# mosfet_buck_inverterV2.net
KiCad netlist of a schematic drawn in EAGLE
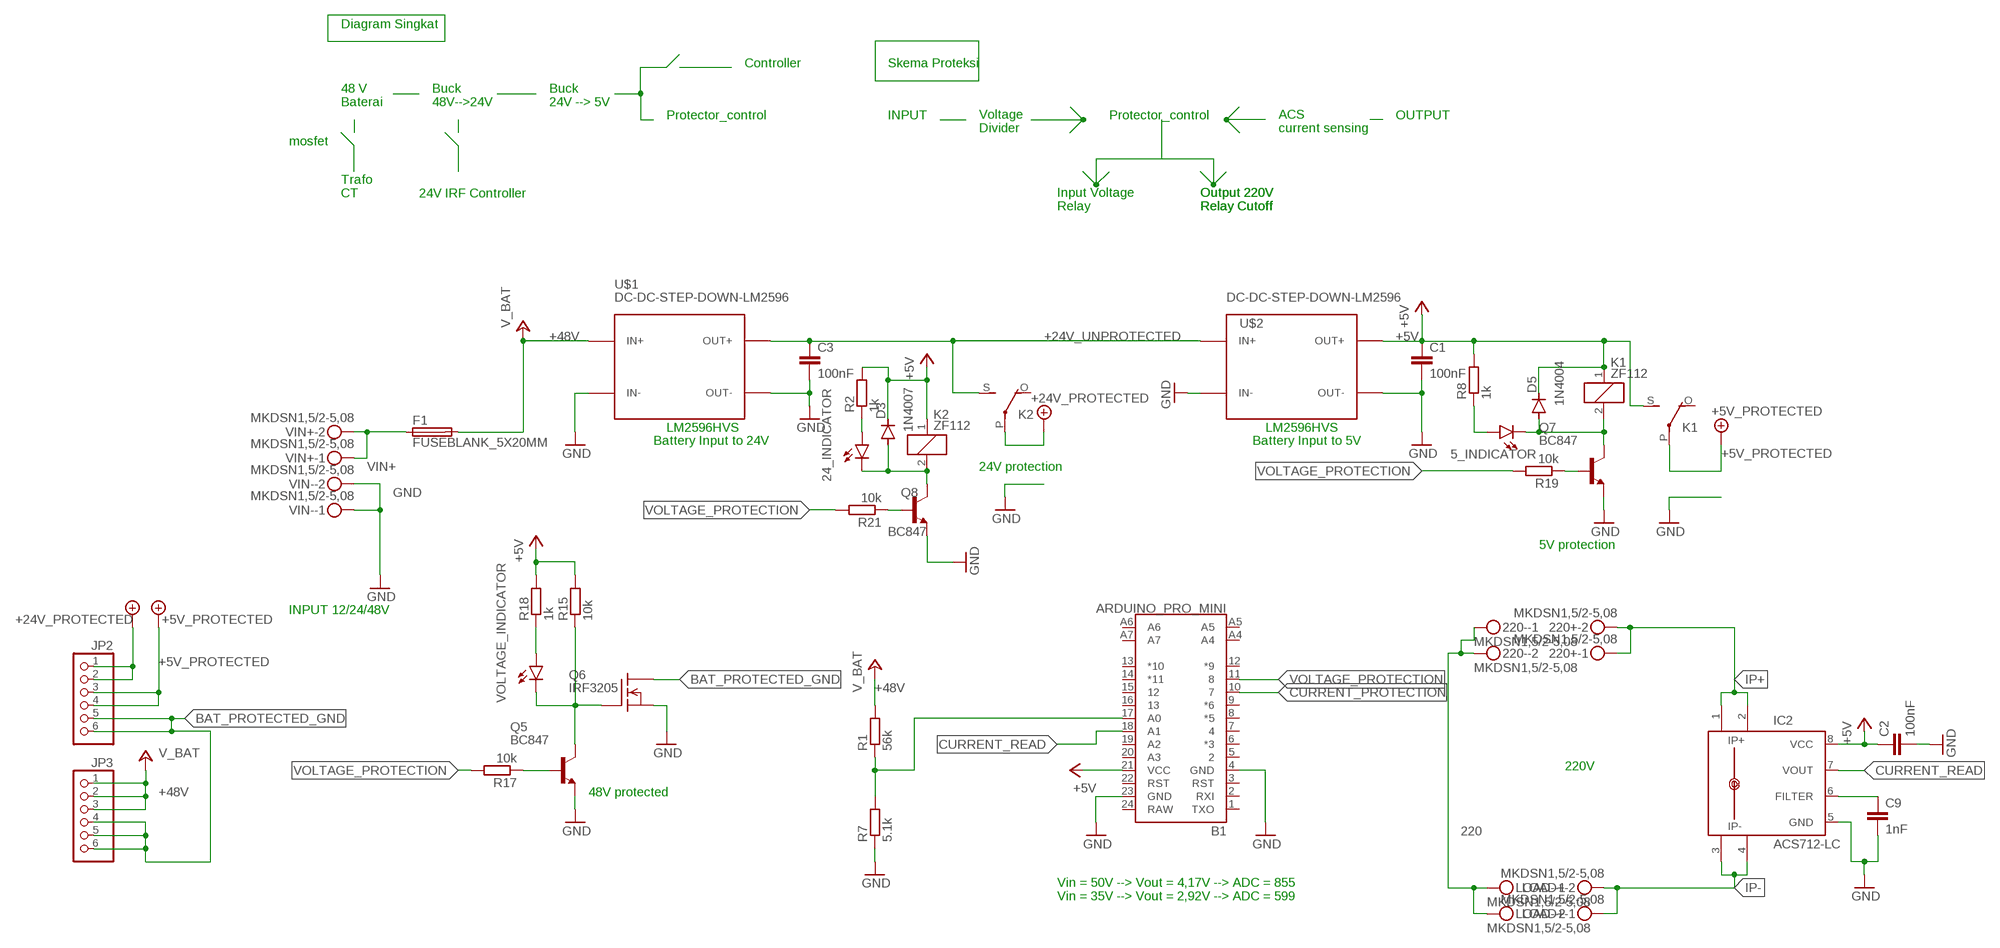
[diagram p0: schematic, sheet 1]

(export (version "E")
  (design (tool "Eeschema 10.0.6"))
  (components
    (comp (ref "5_INDICATOR")
      (value "LED1206")
      (footprint "eagle-import:LED-1206")
      (libsource (lib "eagle-import") (part "LED1206"))
    )
    (comp (ref "24_INDICATOR")
      (value "LED1206")
      (footprint "eagle-import:LED-1206")
      (libsource (lib "eagle-import") (part "LED1206"))
    )
    (comp (ref "220+")
      (value "MKDSN1,5/2-5,08")
      (footprint "eagle-import:MKDSN1,5_2-5,08")
      (libsource (lib "eagle-import") (part "MKDSN1,5/2-5,08"))
    )
    (comp (ref "220-")
      (value "MKDSN1,5/2-5,08")
      (footprint "eagle-import:MKDSN1,5_2-5,08")
      (libsource (lib "eagle-import") (part "MKDSN1,5/2-5,08"))
    )
    (comp (ref "B1")
      (value "ARDUINO_PRO_MINI")
      (footprint "eagle-import:ARDUINO_PRO_MINI")
      (libsource (lib "eagle-import") (part "ARDUINO_PRO_MINI"))
    )
    (comp (ref "C1")
      (value "100nF")
      (footprint "eagle-import:C0805K")
      (libsource (lib "eagle-import") (part "C-EUC0805K"))
    )
    (comp (ref "C2")
      (value "100nF")
      (footprint "eagle-import:C0805K")
      (libsource (lib "eagle-import") (part "C-EUC0805K"))
    )
    (comp (ref "C3")
      (value "100nF")
      (footprint "eagle-import:C0805K")
      (libsource (lib "eagle-import") (part "C-EUC0805K"))
    )
    (comp (ref "C9")
      (value "1nF")
      (footprint "eagle-import:C0805K")
      (libsource (lib "eagle-import") (part "C-EUC0805K"))
    )
    (comp (ref "D3")
      (value "1N4007")
      (footprint "eagle-import:DO41-10")
      (libsource (lib "eagle-import") (part "1N4004"))
    )
    (comp (ref "D5")
      (value "1N4004")
      (footprint "eagle-import:DO41-10")
      (libsource (lib "eagle-import") (part "1N4004"))
    )
    (comp (ref "F1")
      (value "FUSEBLANK_5X20MM")
      (footprint "eagle-import:FUSE_HOLDER_5X20MM")
      (libsource (lib "eagle-import") (part "FUSEBLANK_5X20MM"))
    )
    (comp (ref "IC2")
      (value "ACS712-LC")
      (footprint "eagle-import:SOIC8")
      (fields (field (name "SPICEPREFIX") "X"))
      (libsource (lib "eagle-import") (part "ACS712-LC"))
    )
    (comp (ref "JP2")
      (value "PINHD-1X6CLEAN")
      (footprint "eagle-import:1X06-CLEAN")
      (libsource (lib "eagle-import") (part "PINHD-1X6CLEAN"))
    )
    (comp (ref "JP3")
      (value "PINHD-1X6CLEAN")
      (footprint "eagle-import:1X06-CLEAN")
      (libsource (lib "eagle-import") (part "PINHD-1X6CLEAN"))
    )
    (comp (ref "K1")
      (value "ZF112")
      (footprint "eagle-import:ZF112")
      (libsource (lib "eagle-import") (part "ZF112"))
    )
    (comp (ref "K2")
      (value "ZF112")
      (footprint "eagle-import:ZF112")
      (libsource (lib "eagle-import") (part "ZF112"))
    )
    (comp (ref "LOAD+")
      (value "MKDSN1,5/2-5,08")
      (footprint "eagle-import:MKDSN1,5_2-5,08")
      (libsource (lib "eagle-import") (part "MKDSN1,5/2-5,08"))
    )
    (comp (ref "LOAD-")
      (value "MKDSN1,5/2-5,08")
      (footprint "eagle-import:MKDSN1,5_2-5,08")
      (libsource (lib "eagle-import") (part "MKDSN1,5/2-5,08"))
    )
    (comp (ref "Q5")
      (value "BC847")
      (footprint "eagle-import:SOT23")
      (libsource (lib "eagle-import") (part "BC847SMDA"))
    )
    (comp (ref "Q6")
      (value "IRF3205")
      (footprint "eagle-import:TO220")
      (libsource (lib "eagle-import") (part "IRF540"))
    )
    (comp (ref "Q7")
      (value "BC847")
      (footprint "eagle-import:SOT23")
      (libsource (lib "eagle-import") (part "BC847SMDA"))
    )
    (comp (ref "Q8")
      (value "BC847")
      (footprint "eagle-import:SOT23")
      (libsource (lib "eagle-import") (part "BC847SMDA"))
    )
    (comp (ref "R1")
      (value "56k")
      (footprint "eagle-import:R0805")
      (libsource (lib "eagle-import") (part "R-EU_R0805"))
    )
    (comp (ref "R2")
      (value "1k")
      (footprint "eagle-import:R0805")
      (libsource (lib "eagle-import") (part "R-EU_R0805"))
    )
    (comp (ref "R7")
      (value "5.1k")
      (footprint "eagle-import:R0805")
      (libsource (lib "eagle-import") (part "R-EU_R0805"))
    )
    (comp (ref "R8")
      (value "1k")
      (footprint "eagle-import:R0805")
      (libsource (lib "eagle-import") (part "R-EU_R0805"))
    )
    (comp (ref "R15")
      (value "10k")
      (footprint "eagle-import:R0805")
      (libsource (lib "eagle-import") (part "R-EU_R0805"))
    )
    (comp (ref "R17")
      (value "10k")
      (footprint "eagle-import:R0805")
      (libsource (lib "eagle-import") (part "R-EU_R0805"))
    )
    (comp (ref "R18")
      (value "1k")
      (footprint "eagle-import:R0805")
      (libsource (lib "eagle-import") (part "R-EU_R0805"))
    )
    (comp (ref "R19")
      (value "10k")
      (footprint "eagle-import:R0805")
      (libsource (lib "eagle-import") (part "R-EU_R0805"))
    )
    (comp (ref "R21")
      (value "10k")
      (footprint "eagle-import:R0805")
      (libsource (lib "eagle-import") (part "R-EU_R0805"))
    )
    (comp (ref "U$1")
      (value "DC-DC-STEP-DOWN-LM2596")
      (footprint "eagle-import:DC-DC-STEP-DOWN-LM2596")
      (libsource (lib "eagle-import") (part "DC-DC-STEP-DOWN-LM2596"))
    )
    (comp (ref "U$2")
      (value "DC-DC-STEP-DOWN-LM2596")
      (footprint "eagle-import:DC-DC-STEP-DOWN-LM2596")
      (libsource (lib "eagle-import") (part "DC-DC-STEP-DOWN-LM2596"))
    )
    (comp (ref "VIN+")
      (value "MKDSN1,5/2-5,08")
      (footprint "eagle-import:MKDSN1,5_2-5,08")
      (libsource (lib "eagle-import") (part "MKDSN1,5/2-5,08"))
    )
    (comp (ref "VIN-")
      (value "MKDSN1,5/2-5,08")
      (footprint "eagle-import:MKDSN1,5_2-5,08")
      (libsource (lib "eagle-import") (part "MKDSN1,5/2-5,08"))
    )
    (comp (ref "VOLTAGE_INDICATOR")
      (value "LED1206")
      (footprint "eagle-import:LED-1206")
      (libsource (lib "eagle-import") (part "LED1206"))
    )
  )
  (nets
    (net (code "1") (name "+5V") (class "Default")
      (node (ref "B1") (pin "21") (pinfunction "VCC_21") (pintype "power_in"))
      (node (ref "C1") (pin "1") (pinfunction "1_1") (pintype "passive"))
      (node (ref "C2") (pin "1") (pinfunction "1_1") (pintype "passive"))
      (node (ref "D3") (pin "C") (pinfunction "C_C") (pintype "passive"))
      (node (ref "D5") (pin "C") (pinfunction "C_C") (pintype "passive"))
      (node (ref "IC2") (pin "8") (pinfunction "VCC_8") (pintype "power_in"))
      (node (ref "K1") (pin "1") (pinfunction "1_1") (pintype "passive"))
      (node (ref "K1") (pin "S") (pinfunction "S_S") (pintype "passive"))
      (node (ref "K2") (pin "1") (pinfunction "1_1") (pintype "passive"))
      (node (ref "R15") (pin "2") (pinfunction "2_2") (pintype "passive"))
      (node (ref "R18") (pin "2") (pinfunction "2_2") (pintype "passive"))
      (node (ref "R2") (pin "2") (pinfunction "2_2") (pintype "passive"))
      (node (ref "R8") (pin "2") (pinfunction "2_2") (pintype "passive"))
      (node (ref "U$2") (pin "OUT+") (pinfunction "OUT+_OUT+") (pintype "bidirectional"))
    )
    (net (code "2") (name "+5V_PROTECTED") (class "Default")
      (node (ref "JP2") (pin "3") (pinfunction "3_3") (pintype "passive"))
      (node (ref "JP2") (pin "4") (pinfunction "4_4") (pintype "passive"))
      (node (ref "K1") (pin "P") (pinfunction "P_P") (pintype "passive"))
    )
    (net (code "3") (name "+24V_PROTECTED") (class "Default")
      (node (ref "JP2") (pin "1") (pinfunction "1_1") (pintype "passive"))
      (node (ref "JP2") (pin "2") (pinfunction "2_2") (pintype "passive"))
      (node (ref "K2") (pin "P") (pinfunction "P_P") (pintype "passive"))
    )
    (net (code "4") (name "/+24V_UNPROTECTED") (class "Default")
      (node (ref "C3") (pin "1") (pinfunction "1_1") (pintype "passive"))
      (node (ref "K2") (pin "S") (pinfunction "S_S") (pintype "passive"))
      (node (ref "U$1") (pin "OUT+") (pinfunction "OUT+_OUT+") (pintype "bidirectional"))
      (node (ref "U$2") (pin "IN+") (pinfunction "IN+_IN+") (pintype "bidirectional"))
    )
    (net (code "5") (name "/220") (class "Default")
      (node (ref "220-") (pin "1") (pinfunction "KL_1") (pintype "passive"))
      (node (ref "220-") (pin "2") (pinfunction "KL_2") (pintype "passive"))
      (node (ref "LOAD-") (pin "1") (pinfunction "KL_1") (pintype "passive"))
      (node (ref "LOAD-") (pin "2") (pinfunction "KL_2") (pintype "passive"))
    )
    (net (code "6") (name "/RAW") (class "Default")
      (node (ref "B1") (pin "24") (pinfunction "RAW_24") (pintype "power_in"))
    )
    (net (code "7") (name "/VIN+") (class "Default")
      (node (ref "F1") (pin "1") (pinfunction "1_1") (pintype "passive"))
      (node (ref "VIN+") (pin "1") (pinfunction "KL_1") (pintype "passive"))
      (node (ref "VIN+") (pin "2") (pinfunction "KL_2") (pintype "passive"))
    )
    (net (code "8") (name "BAT_PROTECTED_GND") (class "Default")
      (node (ref "JP2") (pin "5") (pinfunction "5_5") (pintype "passive"))
      (node (ref "JP2") (pin "6") (pinfunction "6_6") (pintype "passive"))
      (node (ref "JP3") (pin "4") (pinfunction "4_4") (pintype "passive"))
      (node (ref "JP3") (pin "5") (pinfunction "5_5") (pintype "passive"))
      (node (ref "JP3") (pin "6") (pinfunction "6_6") (pintype "passive"))
      (node (ref "Q6") (pin "2") (pinfunction "D_2") (pintype "passive"))
    )
    (net (code "9") (name "CURRENT_PROTECTION") (class "Default")
      (node (ref "B1") (pin "10") (pinfunction "7_10") (pintype "bidirectional"))
    )
    (net (code "10") (name "CURRENT_READ") (class "Default")
      (node (ref "B1") (pin "18") (pinfunction "A1_18") (pintype "bidirectional"))
      (node (ref "IC2") (pin "7") (pinfunction "VOUT_7") (pintype "output"))
    )
    (net (code "11") (name "GND") (class "Default")
      (node (ref "B1") (pin "23") (pinfunction "GND_23") (pintype "power_in"))
      (node (ref "B1") (pin "4") (pinfunction "GND_4") (pintype "power_in"))
      (node (ref "C1") (pin "2") (pinfunction "2_2") (pintype "passive"))
      (node (ref "C2") (pin "2") (pinfunction "2_2") (pintype "passive"))
      (node (ref "C3") (pin "2") (pinfunction "2_2") (pintype "passive"))
      (node (ref "C9") (pin "2") (pinfunction "2_2") (pintype "passive"))
      (node (ref "IC2") (pin "5") (pinfunction "GND_5") (pintype "power_in"))
      (node (ref "Q5") (pin "2") (pinfunction "E_2") (pintype "passive"))
      (node (ref "Q6") (pin "3") (pinfunction "S_3") (pintype "passive"))
      (node (ref "Q7") (pin "2") (pinfunction "E_2") (pintype "passive"))
      (node (ref "Q8") (pin "2") (pinfunction "E_2") (pintype "passive"))
      (node (ref "R7") (pin "1") (pinfunction "1_1") (pintype "passive"))
      (node (ref "U$1") (pin "IN-") (pinfunction "IN-_IN-") (pintype "bidirectional"))
      (node (ref "U$1") (pin "OUT-") (pinfunction "OUT-_OUT-") (pintype "bidirectional"))
      (node (ref "U$2") (pin "IN-") (pinfunction "IN-_IN-") (pintype "bidirectional"))
      (node (ref "U$2") (pin "OUT-") (pinfunction "OUT-_OUT-") (pintype "bidirectional"))
      (node (ref "VIN-") (pin "1") (pinfunction "KL_1") (pintype "passive"))
      (node (ref "VIN-") (pin "2") (pinfunction "KL_2") (pintype "passive"))
    )
    (net (code "12") (name "IP+") (class "Default")
      (node (ref "220+") (pin "1") (pinfunction "KL_1") (pintype "passive"))
      (node (ref "220+") (pin "2") (pinfunction "KL_2") (pintype "passive"))
      (node (ref "IC2") (pin "1") (pinfunction "IP+_1") (pintype "passive"))
      (node (ref "IC2") (pin "2") (pinfunction "IP+1_2") (pintype "passive"))
    )
    (net (code "13") (name "IP-") (class "Default")
      (node (ref "IC2") (pin "3") (pinfunction "IP-_3") (pintype "passive"))
      (node (ref "IC2") (pin "4") (pinfunction "IP-1_4") (pintype "passive"))
      (node (ref "LOAD+") (pin "1") (pinfunction "KL_1") (pintype "passive"))
      (node (ref "LOAD+") (pin "2") (pinfunction "KL_2") (pintype "passive"))
    )
    (net (code "14") (name "Net-(5_INDICATOR-PadA)") (class "Default")
      (node (ref "5_INDICATOR") (pin "A") (pinfunction "A_A") (pintype "passive"))
      (node (ref "R8") (pin "1") (pinfunction "1_1") (pintype "passive"))
    )
    (net (code "15") (name "Net-(24_INDICATOR-PadA)") (class "Default")
      (node (ref "24_INDICATOR") (pin "A") (pinfunction "A_A") (pintype "passive"))
      (node (ref "R2") (pin "1") (pinfunction "1_1") (pintype "passive"))
    )
    (net (code "16") (name "Net-(B1-A0)") (class "Default")
      (node (ref "B1") (pin "17") (pinfunction "A0_17") (pintype "bidirectional"))
      (node (ref "R1") (pin "1") (pinfunction "1_1") (pintype "passive"))
      (node (ref "R7") (pin "2") (pinfunction "2_2") (pintype "passive"))
    )
    (net (code "17") (name "Net-(IC2-FILTER)") (class "Default")
      (node (ref "C9") (pin "1") (pinfunction "1_1") (pintype "passive"))
      (node (ref "IC2") (pin "6") (pinfunction "FILTER_6") (pintype "bidirectional"))
    )
    (net (code "18") (name "Net-(Q5-B)") (class "Default")
      (node (ref "Q5") (pin "1") (pinfunction "B_1") (pintype "passive"))
      (node (ref "R17") (pin "1") (pinfunction "1_1") (pintype "passive"))
    )
    (net (code "19") (name "Net-(Q5-C)") (class "Default")
      (node (ref "Q5") (pin "3") (pinfunction "C_3") (pintype "passive"))
      (node (ref "Q6") (pin "1") (pinfunction "G_1") (pintype "passive"))
      (node (ref "R15") (pin "1") (pinfunction "1_1") (pintype "passive"))
      (node (ref "VOLTAGE_INDICATOR") (pin "C") (pinfunction "C_C") (pintype "passive"))
    )
    (net (code "20") (name "Net-(Q7-B)") (class "Default")
      (node (ref "Q7") (pin "1") (pinfunction "B_1") (pintype "passive"))
      (node (ref "R19") (pin "1") (pinfunction "1_1") (pintype "passive"))
    )
    (net (code "21") (name "Net-(Q7-C)") (class "Default")
      (node (ref "5_INDICATOR") (pin "C") (pinfunction "C_C") (pintype "passive"))
      (node (ref "D5") (pin "A") (pinfunction "A_A") (pintype "passive"))
      (node (ref "K1") (pin "2") (pinfunction "2_2") (pintype "passive"))
      (node (ref "Q7") (pin "3") (pinfunction "C_3") (pintype "passive"))
    )
    (net (code "22") (name "Net-(Q8-B)") (class "Default")
      (node (ref "Q8") (pin "1") (pinfunction "B_1") (pintype "passive"))
      (node (ref "R21") (pin "1") (pinfunction "1_1") (pintype "passive"))
    )
    (net (code "23") (name "Net-(Q8-C)") (class "Default")
      (node (ref "24_INDICATOR") (pin "C") (pinfunction "C_C") (pintype "passive"))
      (node (ref "D3") (pin "A") (pinfunction "A_A") (pintype "passive"))
      (node (ref "K2") (pin "2") (pinfunction "2_2") (pintype "passive"))
      (node (ref "Q8") (pin "3") (pinfunction "C_3") (pintype "passive"))
    )
    (net (code "24") (name "Net-(R18-Pad1)") (class "Default")
      (node (ref "R18") (pin "1") (pinfunction "1_1") (pintype "passive"))
      (node (ref "VOLTAGE_INDICATOR") (pin "A") (pinfunction "A_A") (pintype "passive"))
    )
    (net (code "25") (name "VOLTAGE_PROTECTION") (class "Default")
      (node (ref "B1") (pin "11") (pinfunction "8_11") (pintype "bidirectional"))
      (node (ref "R17") (pin "2") (pinfunction "2_2") (pintype "passive"))
      (node (ref "R19") (pin "2") (pinfunction "2_2") (pintype "passive"))
      (node (ref "R21") (pin "2") (pinfunction "2_2") (pintype "passive"))
    )
    (net (code "26") (name "V_BAT") (class "Default")
      (node (ref "F1") (pin "2") (pinfunction "2_2") (pintype "passive"))
      (node (ref "JP3") (pin "1") (pinfunction "1_1") (pintype "passive"))
      (node (ref "JP3") (pin "2") (pinfunction "2_2") (pintype "passive"))
      (node (ref "JP3") (pin "3") (pinfunction "3_3") (pintype "passive"))
      (node (ref "R1") (pin "2") (pinfunction "2_2") (pintype "passive"))
      (node (ref "U$1") (pin "IN+") (pinfunction "IN+_IN+") (pintype "bidirectional"))
    )
    (net (code "27") (name "unconnected-(B1-*3-Pad6)") (class "Default")
      (node (ref "B1") (pin "6") (pinfunction "*3_6") (pintype "bidirectional"))
    )
    (net (code "28") (name "unconnected-(B1-*5-Pad8)") (class "Default")
      (node (ref "B1") (pin "8") (pinfunction "*5_8") (pintype "bidirectional"))
    )
    (net (code "29") (name "unconnected-(B1-*6-Pad9)") (class "Default")
      (node (ref "B1") (pin "9") (pinfunction "*6_9") (pintype "bidirectional"))
    )
    (net (code "30") (name "unconnected-(B1-*9-Pad12)") (class "Default")
      (node (ref "B1") (pin "12") (pinfunction "*9_12") (pintype "bidirectional"))
    )
    (net (code "31") (name "unconnected-(B1-*10-Pad13)") (class "Default")
      (node (ref "B1") (pin "13") (pinfunction "*10_13") (pintype "bidirectional"))
    )
    (net (code "32") (name "unconnected-(B1-*11-Pad14)") (class "Default")
      (node (ref "B1") (pin "14") (pinfunction "*11_14") (pintype "bidirectional"))
    )
    (net (code "33") (name "unconnected-(B1-2-Pad5)") (class "Default")
      (node (ref "B1") (pin "5") (pinfunction "2_5") (pintype "bidirectional"))
    )
    (net (code "34") (name "unconnected-(B1-4-Pad7)") (class "Default")
      (node (ref "B1") (pin "7") (pinfunction "4_7") (pintype "bidirectional"))
    )
    (net (code "35") (name "unconnected-(B1-12-Pad15)") (class "Default")
      (node (ref "B1") (pin "15") (pinfunction "12_15") (pintype "bidirectional"))
    )
    (net (code "36") (name "unconnected-(B1-13-Pad16)") (class "Default")
      (node (ref "B1") (pin "16") (pinfunction "13_16") (pintype "bidirectional"))
    )
    (net (code "37") (name "unconnected-(B1-A2-Pad19)") (class "Default")
      (node (ref "B1") (pin "19") (pinfunction "A2_19") (pintype "bidirectional"))
    )
    (net (code "38") (name "unconnected-(B1-A3-Pad20)") (class "Default")
      (node (ref "B1") (pin "20") (pinfunction "A3_20") (pintype "bidirectional"))
    )
    (net (code "39") (name "unconnected-(B1-PadA4)") (class "Default")
      (node (ref "B1") (pin "A4") (pinfunction "A4_A4") (pintype "bidirectional"))
    )
    (net (code "40") (name "unconnected-(B1-PadA5)") (class "Default")
      (node (ref "B1") (pin "A5") (pinfunction "A5_A5") (pintype "bidirectional"))
    )
    (net (code "41") (name "unconnected-(B1-PadA6)") (class "Default")
      (node (ref "B1") (pin "A6") (pinfunction "A6_A6") (pintype "bidirectional"))
    )
    (net (code "42") (name "unconnected-(B1-PadA7)") (class "Default")
      (node (ref "B1") (pin "A7") (pinfunction "A7_A7") (pintype "bidirectional"))
    )
    (net (code "43") (name "unconnected-(B1-RST-Pad3)") (class "Default")
      (node (ref "B1") (pin "3") (pinfunction "RST_3") (pintype "bidirectional"))
    )
    (net (code "44") (name "unconnected-(B1-RST-Pad22)") (class "Default")
      (node (ref "B1") (pin "22") (pinfunction "RST_22") (pintype "bidirectional"))
    )
    (net (code "45") (name "unconnected-(B1-RXI-Pad2)") (class "Default")
      (node (ref "B1") (pin "2") (pinfunction "RXI_2") (pintype "bidirectional"))
    )
    (net (code "46") (name "unconnected-(B1-TXO-Pad1)") (class "Default")
      (node (ref "B1") (pin "1") (pinfunction "TXO_1") (pintype "bidirectional"))
    )
    (net (code "47") (name "unconnected-(K1-PadO)") (class "Default")
      (node (ref "K1") (pin "O") (pinfunction "O_O") (pintype "passive"))
    )
    (net (code "48") (name "unconnected-(K2-PadO)") (class "Default")
      (node (ref "K2") (pin "O") (pinfunction "O_O") (pintype "passive"))
    )
  )
)
